# Mic_SPK.net
KiCad netlist of a schematic drawn in Altium Designer
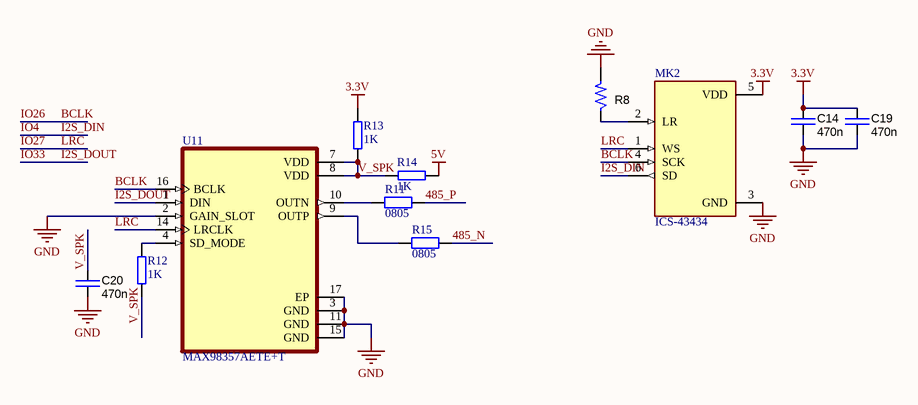
[diagram p0: Mic_SPK.SchDoc]

(export (version "E")
  (design (tool "Eeschema 10.0.6"))
  (components
    (comp (ref "C14")
      (value "470n")
      (footprint "CAPC1608X90N")
      (description "Capacitor SMD Cer 470nF 10% 16V X7R 0603")
      (fields (field (name "TOLERANCE") "±10%"))
      (libsource (lib "My library altium") (part "CAP C_0603"))
    )
    (comp (ref "C19")
      (value "470n")
      (footprint "CAPC1608X90N")
      (description "Capacitor SMD Cer 470nF 10% 16V X7R 0603")
      (fields (field (name "TOLERANCE") "±10%"))
      (libsource (lib "My library altium") (part "CAP C_0603"))
    )
    (comp (ref "C20")
      (value "470n")
      (footprint "CAPC1608X90N")
      (description "Capacitor SMD Cer 470nF 10% 16V X7R 0603")
      (fields (field (name "TOLERANCE") "±10%"))
      (libsource (lib "My library altium") (part "CAP C_0603"))
    )
    (comp (ref "MK2")
      (value "ICS-43434")
      (footprint "MIC_ICS-43434")
      (fields (field (name "MF") "TDK InvenSense"))
      (libsource (lib "ICS-43434") (part "ICS-43434"))
    )
    (comp (ref "R8")
      (value "Thick Film")
      (footprint "RESC1608N_ZERO")
      (description "Resistor SMD chip 0.0 Ohm 0.1W 0603")
      (fields (field (name "TOLERANCE") "±5%"))
      (libsource (lib "My library altium") (part "RES_0603"))
    )
    (comp (ref "R11")
      (value "0805")
      (footprint "DIEN TRO 0805")
      (description "Resistor SMD 0805")
      (fields (field (name "Comment") "R0805") (field (name "PUBLISHER") "Altium Limited"))
      (libsource (lib "My Library") (part "R0805"))
    )
    (comp (ref "R12")
      (value "1K")
      (footprint "SMT0603")
      (description "RES SM 0603 1K")
      (fields (field (name "Comment") "Resistor"))
      (libsource (lib "electronpowered") (part "RES-SM-0603-1K"))
    )
    (comp (ref "R13")
      (value "1K")
      (footprint "SMT0603")
      (description "RES SM 0603 1K")
      (fields (field (name "Comment") "Resistor"))
      (libsource (lib "electronpowered") (part "RES-SM-0603-1K"))
    )
    (comp (ref "R14")
      (value "1K")
      (footprint "SMT0603")
      (description "RES SM 0603 1K")
      (fields (field (name "Comment") "Resistor"))
      (libsource (lib "electronpowered") (part "RES-SM-0603-1K"))
    )
    (comp (ref "R15")
      (value "0805")
      (footprint "DIEN TRO 0805")
      (description "Resistor SMD 0805")
      (fields (field (name "Comment") "R0805") (field (name "PUBLISHER") "Altium Limited"))
      (libsource (lib "My Library") (part "R0805"))
    )
    (comp (ref "U11")
      (value "MAX98357AETE+T")
      (footprint "QFN50P300X300X80-17N")
      (description "Amplifier IC 1-Channel _Mono_ Class D 16-TQFN _3x3_")
      (fields (field (name "MF") "Maxim Integrated"))
      (libsource (lib "MAX98357AETE_T") (part "MAX98357AETE+T"))
    )
  )
  (nets
    (net (code "1") (name "/485_N") (class "Default")
      (node (ref "R15") (pin "2") (pinfunction "2_2") (pintype "passive"))
    )
    (net (code "2") (name "/485_P") (class "Default")
      (node (ref "R11") (pin "2") (pinfunction "2_2") (pintype "passive"))
    )
    (net (code "3") (name "/BCLK") (class "Default")
      (node (ref "MK2") (pin "4") (pinfunction "SCK_4") (pintype "input"))
      (node (ref "U11") (pin "16") (pinfunction "BCLK_16") (pintype "input"))
    )
    (net (code "4") (name "/I2S_DIN") (class "Default")
      (node (ref "MK2") (pin "6") (pinfunction "SD_6") (pintype "output"))
    )
    (net (code "5") (name "/I2S_DOUT") (class "Default")
      (node (ref "U11") (pin "1") (pinfunction "DIN_1") (pintype "input"))
    )
    (net (code "6") (name "/IO27") (class "Default")
      (node (ref "MK2") (pin "1") (pinfunction "WS_1") (pintype "input"))
      (node (ref "U11") (pin "14") (pinfunction "LRCLK_14") (pintype "input"))
    )
    (net (code "7") (name "/V_SPK") (class "Default")
      (node (ref "C20") (pin "1") (pintype "passive"))
      (node (ref "R12") (pin "1") (pinfunction "1_1") (pintype "passive"))
      (node (ref "R13") (pin "1") (pinfunction "1_1") (pintype "passive"))
      (node (ref "R14") (pin "2") (pinfunction "2_2") (pintype "passive"))
      (node (ref "U11") (pin "7") (pinfunction "VDD_7") (pintype "power_in"))
      (node (ref "U11") (pin "8") (pinfunction "VDD_8") (pintype "power_in"))
    )
    (net (code "8") (name "3.3V") (class "Default")
      (node (ref "C14") (pin "2") (pintype "passive"))
      (node (ref "C19") (pin "2") (pintype "passive"))
      (node (ref "MK2") (pin "5") (pinfunction "VDD_5") (pintype "power_in"))
      (node (ref "R13") (pin "2") (pinfunction "2_2") (pintype "passive"))
    )
    (net (code "9") (name "5V") (class "Default")
      (node (ref "R14") (pin "1") (pinfunction "1_1") (pintype "passive"))
    )
    (net (code "10") (name "GND") (class "Default")
      (node (ref "C14") (pin "1") (pintype "passive"))
      (node (ref "C19") (pin "1") (pintype "passive"))
      (node (ref "C20") (pin "2") (pintype "passive"))
      (node (ref "MK2") (pin "3") (pinfunction "GND_3") (pintype "power_in"))
      (node (ref "R8") (pin "2") (pinfunction "2_2") (pintype "passive"))
      (node (ref "U11") (pin "11") (pinfunction "GND_11") (pintype "power_in"))
      (node (ref "U11") (pin "15") (pinfunction "GND_15") (pintype "power_in"))
      (node (ref "U11") (pin "17") (pinfunction "EP_17") (pintype "power_in"))
      (node (ref "U11") (pin "2") (pinfunction "GAIN_SLOT_2") (pintype "input"))
      (node (ref "U11") (pin "3") (pinfunction "GND_3") (pintype "power_in"))
    )
    (net (code "11") (name "Net-(MK2-LR)") (class "Default")
      (node (ref "MK2") (pin "2") (pinfunction "LR_2") (pintype "input"))
      (node (ref "R8") (pin "1") (pinfunction "1_1") (pintype "passive"))
    )
    (net (code "12") (name "Net-(U11-OUTN)") (class "Default")
      (node (ref "R11") (pin "1") (pinfunction "1_1") (pintype "passive"))
      (node (ref "U11") (pin "10") (pinfunction "OUTN_10") (pintype "output"))
    )
    (net (code "13") (name "Net-(U11-OUTP)") (class "Default")
      (node (ref "R15") (pin "1") (pinfunction "1_1") (pintype "passive"))
      (node (ref "U11") (pin "9") (pinfunction "OUTP_9") (pintype "output"))
    )
    (net (code "14") (name "Net-(U11-SD_MODE)") (class "Default")
      (node (ref "R12") (pin "2") (pinfunction "2_2") (pintype "passive"))
      (node (ref "U11") (pin "4") (pinfunction "SD_MODE_4") (pintype "input"))
    )
  )
)
